# Bridge_Digitizer.net
KiCad netlist of a schematic drawn in EAGLE
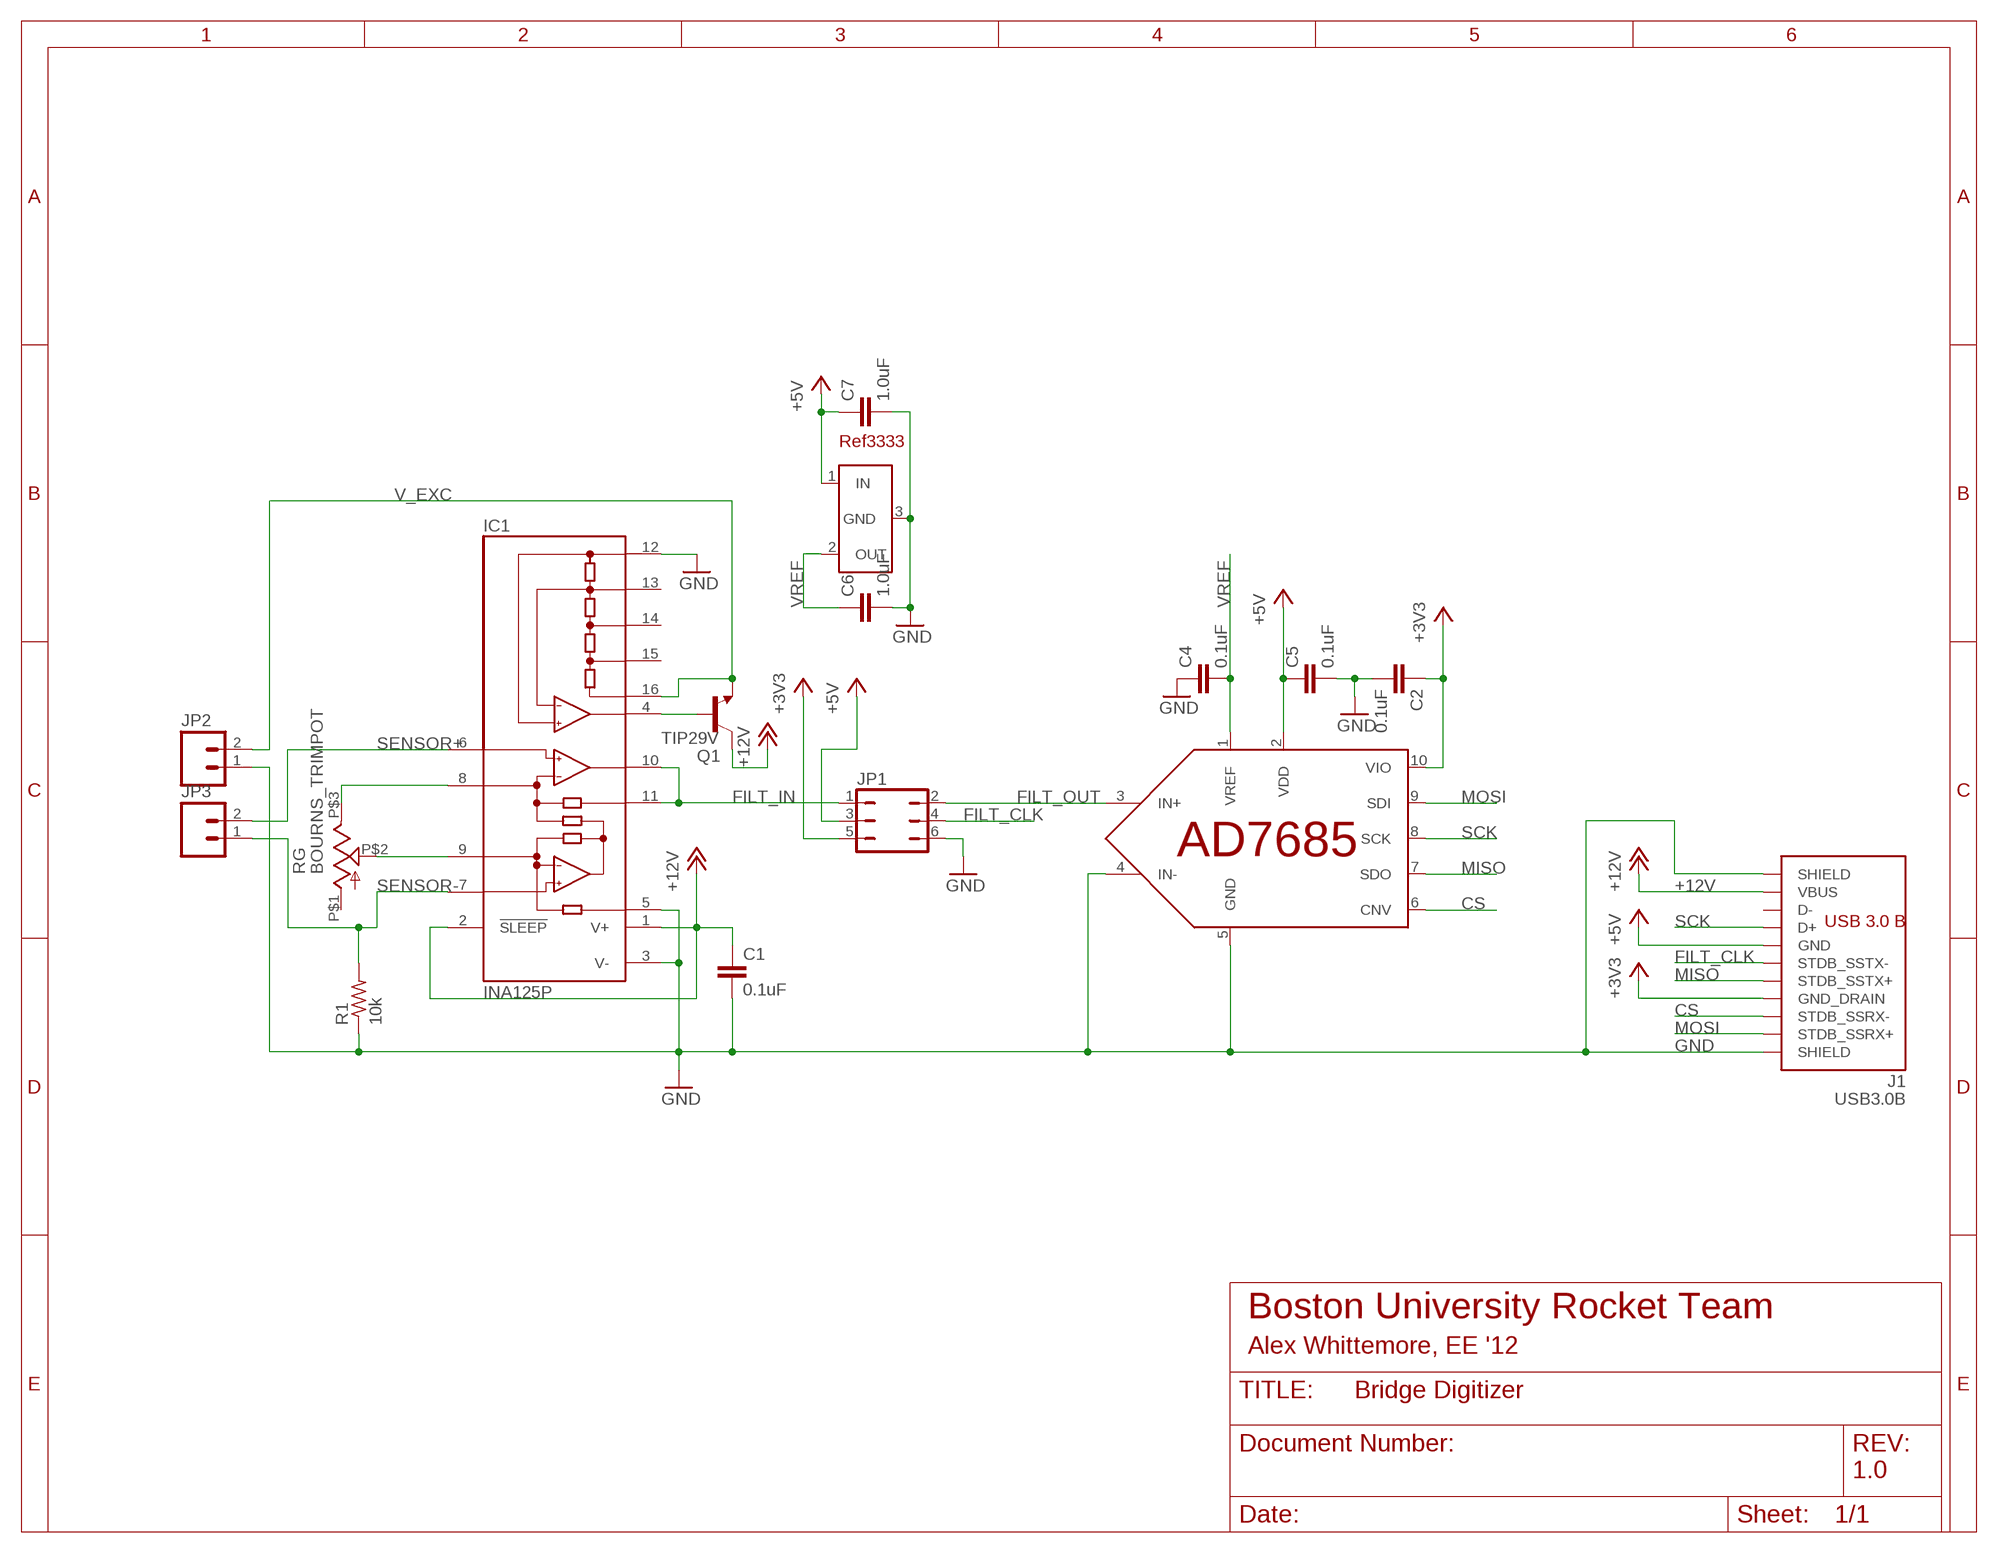
[diagram p0: schematic, sheet 1]

(export (version "E")
  (design (tool "Eeschema 10.0.6"))
  (components
    (comp (ref "C1")
      (value "0.1uF")
      (footprint "eagle-import:0402-CAP")
      (libsource (lib "eagle-import") (part "CAP0402-CAP"))
    )
    (comp (ref "C2")
      (value "0.1uF")
      (footprint "eagle-import:0402-CAP")
      (libsource (lib "eagle-import") (part "CAP0402-CAP"))
    )
    (comp (ref "C4")
      (value "0.1uF")
      (footprint "eagle-import:0402-CAP")
      (libsource (lib "eagle-import") (part "CAP0402-CAP"))
    )
    (comp (ref "C5")
      (value "0.1uF")
      (footprint "eagle-import:0402-CAP")
      (libsource (lib "eagle-import") (part "CAP0402-CAP"))
    )
    (comp (ref "C6")
      (value "1.0uF")
      (footprint "eagle-import:0402-CAP")
      (libsource (lib "eagle-import") (part "CAP0402-CAP"))
    )
    (comp (ref "C7")
      (value "1.0uF")
      (footprint "eagle-import:0402-CAP")
      (libsource (lib "eagle-import") (part "CAP0402-CAP"))
    )
    (comp (ref "IC1")
      (value "INA125P")
      (footprint "eagle-import:DIL16")
      (fields (field (name "MF") "TEXAS INSTRUMENT CONNECTORS"))
      (libsource (lib "eagle-import") (part "INA125P"))
    )
    (comp (ref "IC3")
      (value "AD7685")
      (footprint "eagle-import:MSOP10")
      (libsource (lib "eagle-import") (part "AD7685"))
    )
    (comp (ref "IC4")
      (value "REF3333")
      (footprint "eagle-import:SOT23")
      (libsource (lib "eagle-import") (part "REF3333"))
    )
    (comp (ref "J1")
      (value "USB3.0B")
      (footprint "eagle-import:AMPHENOLUSB3.0B")
      (libsource (lib "eagle-import") (part "USB3.0B"))
    )
    (comp (ref "JP1")
      (value "JP3Q")
      (footprint "eagle-import:JP3Q")
      (libsource (lib "eagle-import") (part "JP3Q"))
    )
    (comp (ref "JP2")
      (value "M025MM")
      (footprint "eagle-import:SCREWTERMINAL-5MM-2")
      (libsource (lib "eagle-import") (part "M025MM"))
    )
    (comp (ref "JP3")
      (value "M025MM")
      (footprint "eagle-import:SCREWTERMINAL-5MM-2")
      (libsource (lib "eagle-import") (part "M025MM"))
    )
    (comp (ref "Q1")
      (value "TIP29V")
      (footprint "eagle-import:TO220V")
      (libsource (lib "eagle-import") (part "TIP29V"))
    )
    (comp (ref "R1")
      (value "10k")
      (footprint "eagle-import:0207_7")
      (libsource (lib "eagle-import") (part "R-US_0207/7"))
    )
    (comp (ref "RG")
      (value "BOURNS_TRIMPOT")
      (footprint "eagle-import:3296W")
      (libsource (lib "eagle-import") (part "BOURNS_TRIMPOT"))
    )
  )
  (nets
    (net (code "1") (name "+3V3") (class "Default")
      (node (ref "C2") (pin "1") (pinfunction "1_1") (pintype "passive"))
      (node (ref "IC3") (pin "10") (pinfunction "VIO_10") (pintype "input"))
      (node (ref "J1") (pin "7") (pinfunction "GND_DRAIN_7") (pintype "bidirectional"))
      (node (ref "JP1") (pin "5") (pinfunction "5_5") (pintype "passive"))
    )
    (net (code "2") (name "+5V") (class "Default")
      (node (ref "C5") (pin "1") (pinfunction "1_1") (pintype "passive"))
      (node (ref "C7") (pin "1") (pinfunction "1_1") (pintype "passive"))
      (node (ref "IC3") (pin "2") (pinfunction "VDD_2") (pintype "power_in"))
      (node (ref "IC4") (pin "1") (pinfunction "IN_1") (pintype "power_in"))
      (node (ref "J1") (pin "4") (pinfunction "GND_4") (pintype "bidirectional"))
      (node (ref "JP1") (pin "3") (pinfunction "3_3") (pintype "passive"))
    )
    (net (code "3") (name "+12V") (class "Default")
      (node (ref "C1") (pin "1") (pinfunction "1_1") (pintype "passive"))
      (node (ref "IC1") (pin "1") (pinfunction "V+_1") (pintype "power_in"))
      (node (ref "IC1") (pin "2") (pinfunction "~{SLEEP}_2") (pintype "input"))
      (node (ref "J1") (pin "1") (pinfunction "VBUS_1") (pintype "bidirectional"))
      (node (ref "Q1") (pin "2") (pinfunction "C_2") (pintype "passive"))
    )
    (net (code "4") (name "/CS") (class "Default")
      (node (ref "IC3") (pin "6") (pinfunction "CNV_6") (pintype "input"))
      (node (ref "J1") (pin "8") (pinfunction "STDB_SSRX-_8") (pintype "bidirectional"))
    )
    (net (code "5") (name "/FILT_CLK") (class "Default")
      (node (ref "J1") (pin "5") (pinfunction "STDB_SSTX-_5") (pintype "bidirectional"))
      (node (ref "JP1") (pin "4") (pinfunction "4_4") (pintype "passive"))
    )
    (net (code "6") (name "/FILT_IN") (class "Default")
      (node (ref "IC1") (pin "10") (pinfunction "OUT_10") (pintype "output"))
      (node (ref "IC1") (pin "11") (pinfunction "SENSE_11") (pintype "passive"))
      (node (ref "JP1") (pin "1") (pinfunction "1_1") (pintype "passive"))
    )
    (net (code "7") (name "/FILT_OUT") (class "Default")
      (node (ref "IC3") (pin "3") (pinfunction "IN+_3") (pintype "input"))
      (node (ref "JP1") (pin "2") (pinfunction "2_2") (pintype "passive"))
    )
    (net (code "8") (name "/MISO") (class "Default")
      (node (ref "IC3") (pin "7") (pinfunction "SDO_7") (pintype "output"))
      (node (ref "J1") (pin "6") (pinfunction "STDB_SSTX+_6") (pintype "bidirectional"))
    )
    (net (code "9") (name "/MOSI") (class "Default")
      (node (ref "IC3") (pin "9") (pinfunction "SDI_9") (pintype "input"))
      (node (ref "J1") (pin "9") (pinfunction "STDB_SSRX+_9") (pintype "bidirectional"))
    )
    (net (code "10") (name "/SCK") (class "Default")
      (node (ref "IC3") (pin "8") (pinfunction "SCK_8") (pintype "input"))
      (node (ref "J1") (pin "3") (pinfunction "D+_3") (pintype "bidirectional"))
    )
    (net (code "11") (name "/SENSOR+") (class "Default")
      (node (ref "IC1") (pin "6") (pinfunction "+IN_6") (pintype "input"))
      (node (ref "JP3") (pin "2") (pinfunction "2_2") (pintype "passive"))
    )
    (net (code "12") (name "/SENSOR-") (class "Default")
      (node (ref "IC1") (pin "7") (pinfunction "-IN_7") (pintype "input"))
      (node (ref "JP3") (pin "1") (pinfunction "1_1") (pintype "passive"))
      (node (ref "R1") (pin "2") (pinfunction "2_2") (pintype "passive"))
    )
    (net (code "13") (name "/VREF") (class "Default")
      (node (ref "C4") (pin "2") (pinfunction "2_2") (pintype "passive"))
      (node (ref "C6") (pin "1") (pinfunction "1_1") (pintype "passive"))
      (node (ref "IC3") (pin "1") (pinfunction "VREF_1") (pintype "input"))
      (node (ref "IC4") (pin "2") (pinfunction "OUT_2") (pintype "power_in"))
    )
    (net (code "14") (name "/V_EXC") (class "Default")
      (node (ref "IC1") (pin "16") (pinfunction "REF10_16") (pintype "output"))
      (node (ref "JP2") (pin "2") (pinfunction "2_2") (pintype "passive"))
      (node (ref "Q1") (pin "3") (pinfunction "E_3") (pintype "passive"))
    )
    (net (code "15") (name "GND") (class "Default")
      (node (ref "C1") (pin "2") (pinfunction "2_2") (pintype "passive"))
      (node (ref "C2") (pin "2") (pinfunction "2_2") (pintype "passive"))
      (node (ref "C4") (pin "1") (pinfunction "1_1") (pintype "passive"))
      (node (ref "C5") (pin "2") (pinfunction "2_2") (pintype "passive"))
      (node (ref "C6") (pin "2") (pinfunction "2_2") (pintype "passive"))
      (node (ref "C7") (pin "2") (pinfunction "2_2") (pintype "passive"))
      (node (ref "IC1") (pin "12") (pinfunction "REFCOM_12") (pintype "passive"))
      (node (ref "IC1") (pin "3") (pinfunction "V-_3") (pintype "power_in"))
      (node (ref "IC1") (pin "5") (pinfunction "REF_5") (pintype "passive"))
      (node (ref "IC3") (pin "4") (pinfunction "IN-_4") (pintype "input"))
      (node (ref "IC3") (pin "5") (pinfunction "GND_5") (pintype "power_in"))
      (node (ref "IC4") (pin "3") (pinfunction "GND_3") (pintype "power_in"))
      (node (ref "J1") (pin "10@1") (pinfunction "SHIELD_10@1") (pintype "bidirectional"))
      (node (ref "J1") (pin "10@2") (pinfunction "SHIELD_10@2") (pintype "bidirectional"))
      (node (ref "JP1") (pin "6") (pinfunction "6_6") (pintype "passive"))
      (node (ref "JP2") (pin "1") (pinfunction "1_1") (pintype "passive"))
      (node (ref "R1") (pin "1") (pinfunction "1_1") (pintype "passive"))
    )
    (net (code "16") (name "Net-(IC1-REFOUT)") (class "Default")
      (node (ref "IC1") (pin "4") (pinfunction "REFOUT_4") (pintype "output"))
      (node (ref "Q1") (pin "1") (pinfunction "B_1") (pintype "passive"))
    )
    (net (code "17") (name "Net-(RG-2)") (class "Default")
      (node (ref "IC1") (pin "9") (pinfunction "RG_9") (pintype "passive"))
      (node (ref "RG") (pin "P$2") (pinfunction "2_P$2") (pintype "passive"))
    )
    (net (code "18") (name "Net-(RG-3)") (class "Default")
      (node (ref "IC1") (pin "8") (pinfunction "RG_8") (pintype "passive"))
      (node (ref "RG") (pin "P$3") (pinfunction "3_P$3") (pintype "passive"))
    )
    (net (code "19") (name "unconnected-(IC1-REF2.5-Pad14)") (class "Default")
      (node (ref "IC1") (pin "14") (pinfunction "REF2.5_14") (pintype "output"))
    )
    (net (code "20") (name "unconnected-(IC1-REF5-Pad15)") (class "Default")
      (node (ref "IC1") (pin "15") (pinfunction "REF5_15") (pintype "output"))
    )
    (net (code "21") (name "unconnected-(IC1-REFBG-Pad13)") (class "Default")
      (node (ref "IC1") (pin "13") (pinfunction "REFBG_13") (pintype "output"))
    )
    (net (code "22") (name "unconnected-(J1-D--Pad2)") (class "Default")
      (node (ref "J1") (pin "2") (pinfunction "D-_2") (pintype "bidirectional"))
    )
    (net (code "23") (name "unconnected-(RG-1-PadP$1)") (class "Default")
      (node (ref "RG") (pin "P$1") (pinfunction "1_P$1") (pintype "passive"))
    )
  )
)
